# main.net
KiCad netlist of a schematic drawn in Altium Designer
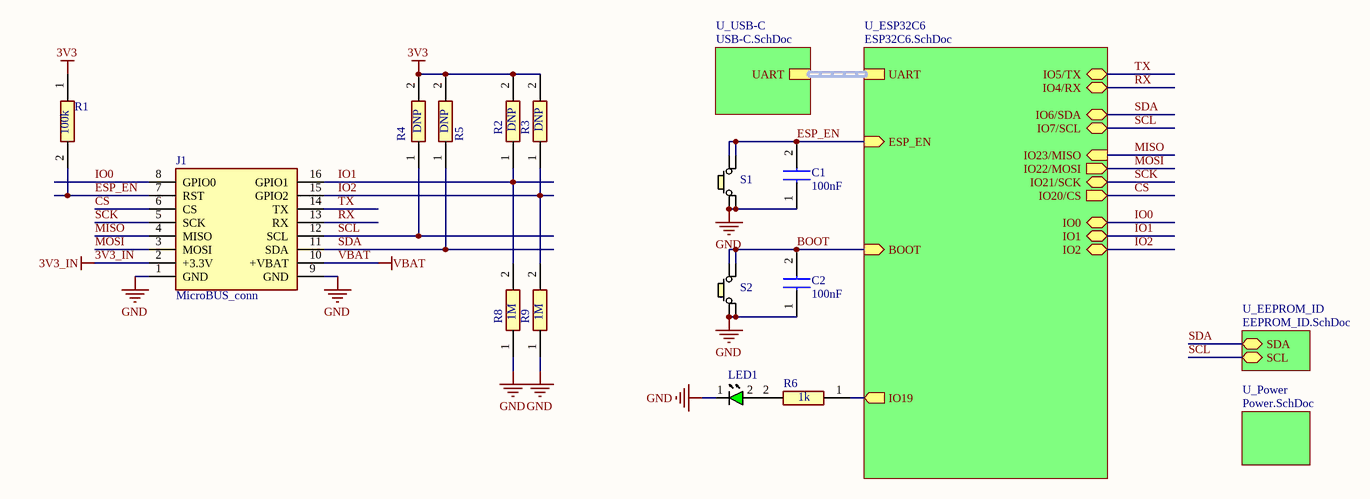
[diagram p0: main.SchDoc]

(export (version "E")
  (design (tool "Eeschema 10.0.6"))
  (components
    (comp (ref "C1")
      (value "100nF")
      (footprint "SamacSys:CAPC1005X70N")
      (description "Capacitor")
      (fields
        (field (name "MANUFACTURER_PART_NUMBER") "GRM155R61A104KA01D")
        (field (name "MOUSER PART NUMBER") "81-GRM155R61A104KA01")
      )
      (libsource (lib "*") (part "GRM155R61A104KA01D"))
    )
    (comp (ref "C2")
      (value "100nF")
      (footprint "SamacSys:CAPC1005X70N")
      (description "Capacitor")
      (fields
        (field (name "MANUFACTURER_PART_NUMBER") "GRM155R61A104KA01D")
        (field (name "MOUSER PART NUMBER") "81-GRM155R61A104KA01")
      )
      (libsource (lib "*") (part "GRM155R61A104KA01D"))
    )
    (comp (ref "J1")
      (value "MicroBUS_conn")
      (footprint "MicroBUS_header")
      (description "Connector")
      (fields
        (field (name "MANUFACTURER_PART_NUMBER") "M20-9730845")
        (field (name "MOUSER PART NUMBER") "855-M20-9730845")
      )
      (libsource (lib "SamacSys") (part "MicroBUS_conn"))
    )
    (comp (ref "LED1")
      (value "150060GS75000")
      (footprint "SamacSys:LEDC1608X80N")
      (description "LED")
      (fields (field (name "MOUSER PART NUMBER") "710-150060GS75000"))
      (libsource (lib "SamacSys") (part "150060GS75000"))
    )
    (comp (ref "R1")
      (value "100k")
      (footprint "SamacSys:RESC1005X35N")
      (description "Resistor")
      (fields
        (field (name "MANUFACTURER_PART_NUMBER") "RT0402FRE07100KL")
        (field (name "MOUSER PART NUMBER") "603-RT0402FRE07100KL")
      )
      (libsource (lib "*") (part "RT0402FRE07100KL"))
    )
    (comp (ref "R2")
      (value "DNP")
      (footprint "SamacSys:RESC1005X40N")
      (description "Resistor")
      (fields
        (field (name "MANUFACTURER_PART_NUMBER") "RC0402FR-071ML")
        (field (name "MOUSER PART NUMBER") "603-RC0402FR-071ML")
      )
      (libsource (lib "*") (part "RC0402FR-071ML"))
    )
    (comp (ref "R3")
      (value "DNP")
      (footprint "SamacSys:RESC1005X40N")
      (description "Resistor")
      (fields
        (field (name "MANUFACTURER_PART_NUMBER") "RC0402FR-071ML")
        (field (name "MOUSER PART NUMBER") "603-RC0402FR-071ML")
      )
      (libsource (lib "*") (part "RC0402FR-071ML"))
    )
    (comp (ref "R4")
      (value "DNP")
      (footprint "SamacSys:RESC1005X35N")
      (description "Resistor")
      (fields (field (name "MANUFACTURER_PART_NUMBER") "RT0402FRE075K1L"))
      (libsource (lib "SamacSys") (part "RT0402FRE075K1L"))
    )
    (comp (ref "R5")
      (value "DNP")
      (footprint "SamacSys:RESC1005X35N")
      (description "Resistor")
      (fields (field (name "MANUFACTURER_PART_NUMBER") "RT0402FRE075K1L"))
      (libsource (lib "SamacSys") (part "RT0402FRE075K1L"))
    )
    (comp (ref "R6")
      (value "1k")
      (footprint "SamacSys:RESC1005X35N")
      (description "Resistor")
      (fields
        (field (name "MANUFACTURER_PART_NUMBER") "RT0402FRE071KL")
        (field (name "ARROW PART NUMBER") "RT0402FRE07100KL")
      )
      (libsource (lib "SamacSys") (part "RT0402FRE071KL"))
    )
    (comp (ref "R8")
      (value "1M")
      (footprint "SamacSys:RESC1005X40N")
      (description "Resistor")
      (fields
        (field (name "MANUFACTURER_PART_NUMBER") "RC0402FR-071ML")
        (field (name "MOUSER PART NUMBER") "603-RC0402FR-071ML")
      )
      (libsource (lib "*") (part "RC0402FR-071ML"))
    )
    (comp (ref "R9")
      (value "1M")
      (footprint "SamacSys:RESC1005X40N")
      (description "Resistor")
      (fields
        (field (name "MANUFACTURER_PART_NUMBER") "RC0402FR-071ML")
        (field (name "MOUSER PART NUMBER") "603-RC0402FR-071ML")
      )
      (libsource (lib "*") (part "RC0402FR-071ML"))
    )
    (comp (ref "S1")
      (value "KMR731NG_LFS")
      (footprint "SamacSys:KMR731NGLFS")
      (description "Switch")
      (fields
        (field (name "MANUFACTURER_PART_NUMBER") "KMR731NG LFS")
        (field (name "MOUSER PART NUMBER") "611-KMR731NGLFS")
      )
      (libsource (lib "SamacSys") (part "KMR731NG_LFS"))
    )
    (comp (ref "S2")
      (value "KMR731NG_LFS")
      (footprint "SamacSys:KMR731NGLFS")
      (description "Switch")
      (fields
        (field (name "MANUFACTURER_PART_NUMBER") "KMR731NG LFS")
        (field (name "MOUSER PART NUMBER") "611-KMR731NGLFS")
      )
      (libsource (lib "SamacSys") (part "KMR731NG_LFS"))
    )
  )
  (nets
    (net (code "1") (name "/BOOT") (class "Default")
      (node (ref "C2") (pin "2") (pinfunction "2_2") (pintype "passive"))
      (node (ref "S2") (pin "3") (pinfunction "3_3") (pintype "passive"))
      (node (ref "S2") (pin "4") (pinfunction "4_4") (pintype "passive"))
    )
    (net (code "2") (name "/CS") (class "Default")
      (node (ref "J1") (pin "6") (pinfunction "CS_6") (pintype "passive"))
    )
    (net (code "3") (name "/ESP_EN") (class "Default")
      (node (ref "C1") (pin "2") (pinfunction "2_2") (pintype "passive"))
      (node (ref "J1") (pin "7") (pinfunction "RST_7") (pintype "passive"))
      (node (ref "R1") (pin "2") (pinfunction "2_2") (pintype "passive"))
      (node (ref "S1") (pin "3") (pinfunction "3_3") (pintype "passive"))
      (node (ref "S1") (pin "4") (pinfunction "4_4") (pintype "passive"))
    )
    (net (code "4") (name "/IO0") (class "Default")
      (node (ref "J1") (pin "8") (pinfunction "GPIO0_8") (pintype "passive"))
    )
    (net (code "5") (name "/IO1") (class "Default")
      (node (ref "J1") (pin "16") (pinfunction "GPIO1_16") (pintype "passive"))
      (node (ref "R2") (pin "1") (pinfunction "1_1") (pintype "passive"))
      (node (ref "R8") (pin "2") (pinfunction "2_2") (pintype "passive"))
    )
    (net (code "6") (name "/IO2") (class "Default")
      (node (ref "J1") (pin "15") (pinfunction "GPIO2_15") (pintype "passive"))
      (node (ref "R3") (pin "1") (pinfunction "1_1") (pintype "passive"))
      (node (ref "R9") (pin "2") (pinfunction "2_2") (pintype "passive"))
    )
    (net (code "7") (name "/IO19") (class "Default")
      (node (ref "R6") (pin "1") (pinfunction "1_1") (pintype "passive"))
    )
    (net (code "8") (name "/MISO") (class "Default")
      (node (ref "J1") (pin "4") (pinfunction "MISO_4") (pintype "passive"))
    )
    (net (code "9") (name "/MOSI") (class "Default")
      (node (ref "J1") (pin "3") (pinfunction "MOSI_3") (pintype "passive"))
    )
    (net (code "10") (name "/RX") (class "Default")
      (node (ref "J1") (pin "13") (pinfunction "RX_13") (pintype "passive"))
    )
    (net (code "11") (name "/SCK") (class "Default")
      (node (ref "J1") (pin "5") (pinfunction "SCK_5") (pintype "passive"))
    )
    (net (code "12") (name "/SCL") (class "Default")
      (node (ref "J1") (pin "12") (pinfunction "SCL_12") (pintype "passive"))
      (node (ref "R4") (pin "1") (pinfunction "1_1") (pintype "passive"))
    )
    (net (code "13") (name "/SDA") (class "Default")
      (node (ref "J1") (pin "11") (pinfunction "SDA_11") (pintype "passive"))
      (node (ref "R5") (pin "1") (pinfunction "1_1") (pintype "passive"))
    )
    (net (code "14") (name "/TX") (class "Default")
      (node (ref "J1") (pin "14") (pinfunction "TX_14") (pintype "passive"))
    )
    (net (code "16") (name "3V3") (class "Default")
      (node (ref "R1") (pin "1") (pinfunction "1_1") (pintype "passive"))
      (node (ref "R2") (pin "2") (pinfunction "2_2") (pintype "passive"))
      (node (ref "R3") (pin "2") (pinfunction "2_2") (pintype "passive"))
      (node (ref "R4") (pin "2") (pinfunction "2_2") (pintype "passive"))
      (node (ref "R5") (pin "2") (pinfunction "2_2") (pintype "passive"))
    )
    (net (code "17") (name "3V3_IN") (class "Default")
      (node (ref "J1") (pin "2") (pinfunction "+3.3V_2") (pintype "passive"))
    )
    (net (code "18") (name "GND") (class "Default")
      (node (ref "C1") (pin "1") (pinfunction "1_1") (pintype "passive"))
      (node (ref "C2") (pin "1") (pinfunction "1_1") (pintype "passive"))
      (node (ref "J1") (pin "1") (pinfunction "GND_1") (pintype "passive"))
      (node (ref "J1") (pin "9") (pinfunction "GND_9") (pintype "passive"))
      (node (ref "LED1") (pin "1") (pinfunction "K_1") (pintype "passive"))
      (node (ref "R8") (pin "1") (pinfunction "1_1") (pintype "passive"))
      (node (ref "R9") (pin "1") (pinfunction "1_1") (pintype "passive"))
      (node (ref "S1") (pin "1") (pinfunction "1_1") (pintype "passive"))
      (node (ref "S1") (pin "2") (pinfunction "2_2") (pintype "passive"))
      (node (ref "S2") (pin "1") (pinfunction "1_1") (pintype "passive"))
      (node (ref "S2") (pin "2") (pinfunction "2_2") (pintype "passive"))
    )
    (net (code "19") (name "Net-(LED1-A)") (class "Default")
      (node (ref "LED1") (pin "2") (pinfunction "A_2") (pintype "passive"))
      (node (ref "R6") (pin "2") (pinfunction "2_2") (pintype "passive"))
    )
    (net (code "20") (name "VBAT") (class "Default")
      (node (ref "J1") (pin "10") (pinfunction "+VBAT_10") (pintype "passive"))
    )
  )
)
